# mainboard.net
KiCad netlist of a schematic drawn in EAGLE
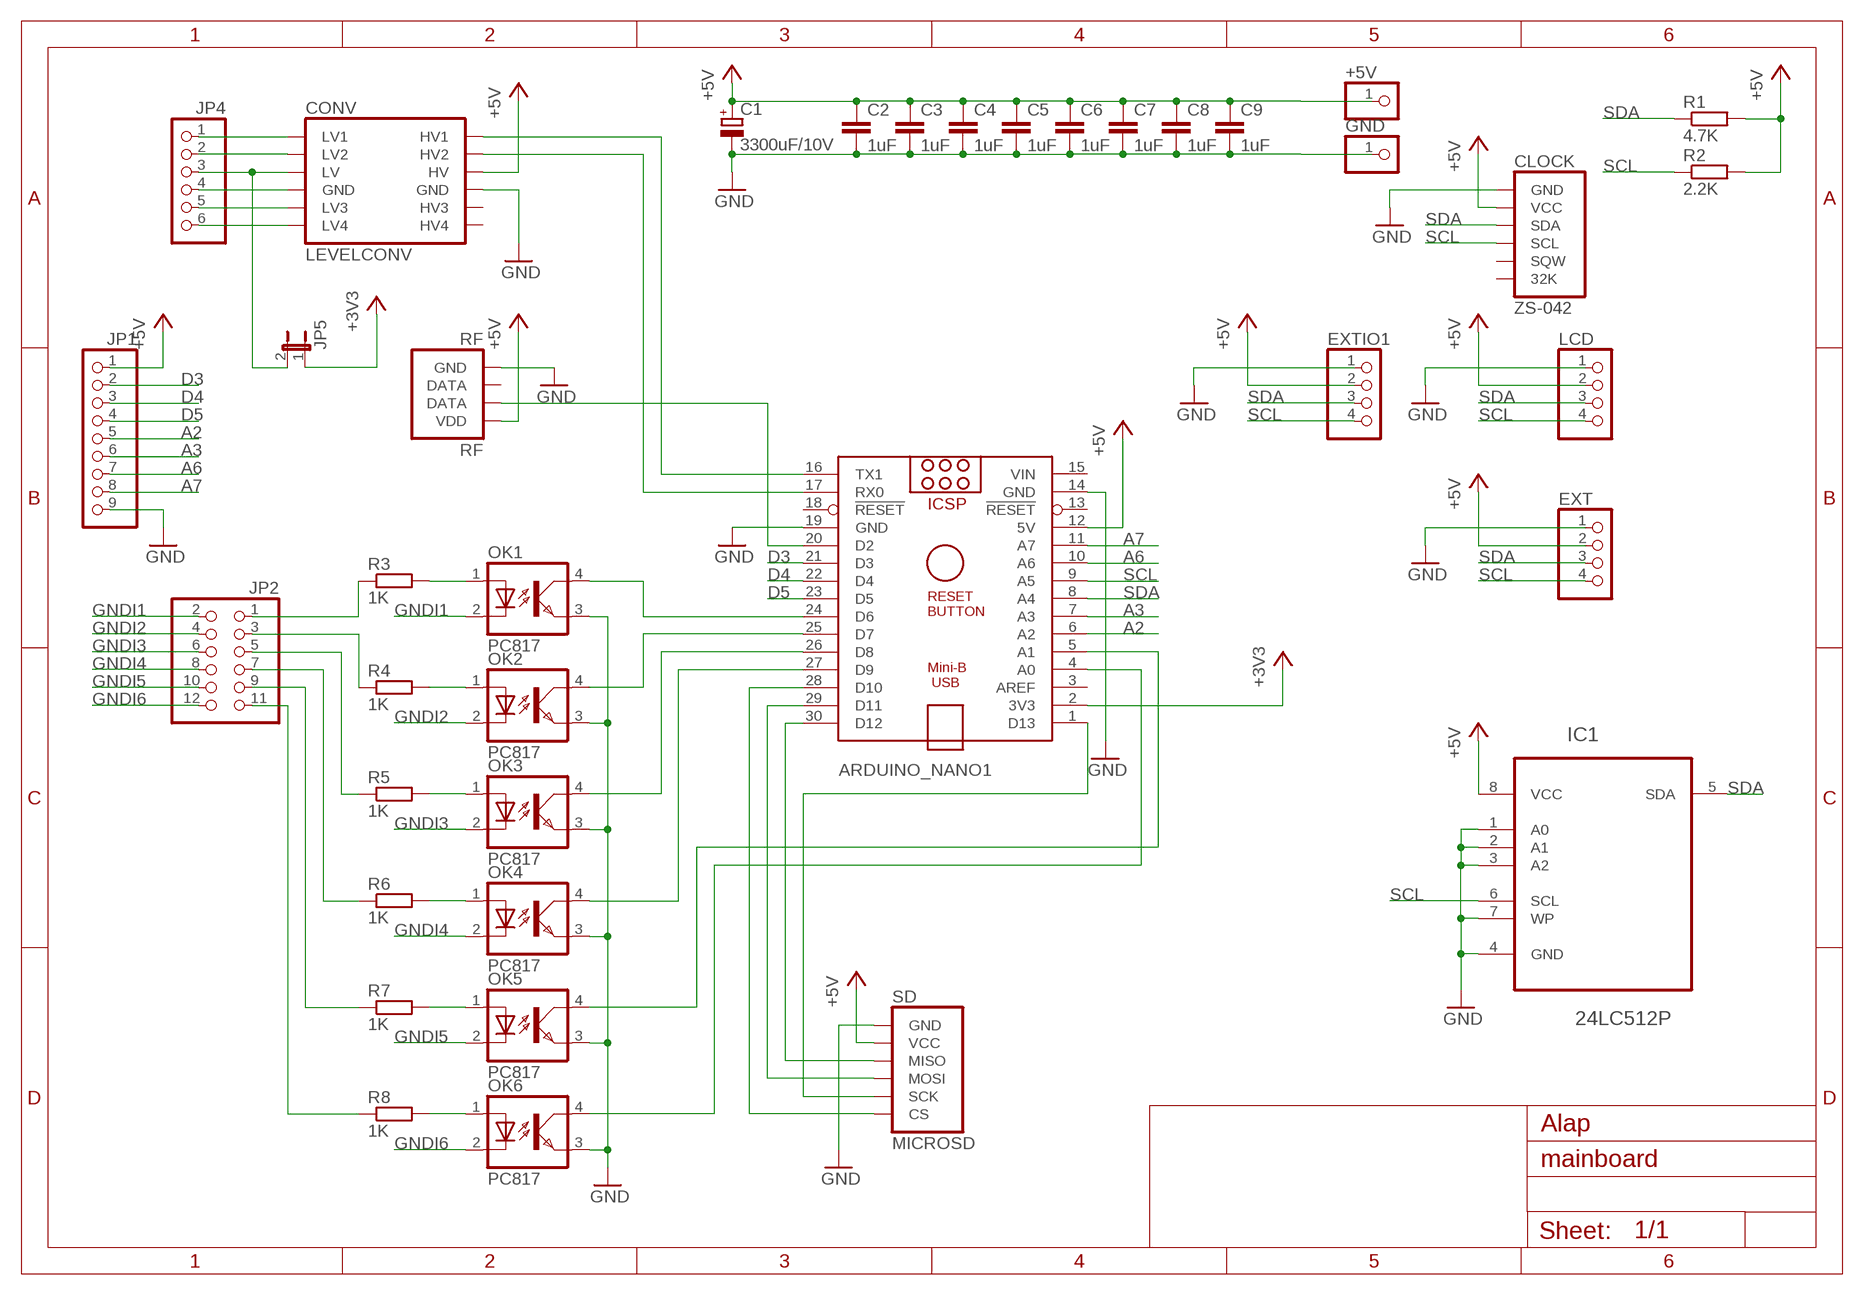
[diagram p0: schematic, sheet 1]

(export (version "E")
  (design (tool "Eeschema 10.0.6"))
  (components
    (comp (ref "+5V")
      (value "PINHD-1X1")
      (footprint "eagle-import:1X01")
      (libsource (lib "eagle-import") (part "PINHD-1X1"))
    )
    (comp (ref "ARDUINO_NANO1")
      (value "ARDUINO_NANO")
      (footprint "eagle-import:ARDUINO_NANO")
      (libsource (lib "eagle-import") (part "ARDUINO_NANO"))
    )
    (comp (ref "C1")
      (value "3300uF/10V")
      (footprint "eagle-import:E5-10,5")
      (libsource (lib "eagle-import") (part "CPOL-EUE5-10.5"))
    )
    (comp (ref "C2")
      (value "1uF")
      (footprint "eagle-import:C0603")
      (libsource (lib "eagle-import") (part "C-EUC0603"))
    )
    (comp (ref "C3")
      (value "1uF")
      (footprint "eagle-import:C0603")
      (libsource (lib "eagle-import") (part "C-EUC0603"))
    )
    (comp (ref "C4")
      (value "1uF")
      (footprint "eagle-import:C0603")
      (libsource (lib "eagle-import") (part "C-EUC0603"))
    )
    (comp (ref "C5")
      (value "1uF")
      (footprint "eagle-import:C0603")
      (libsource (lib "eagle-import") (part "C-EUC0603"))
    )
    (comp (ref "C6")
      (value "1uF")
      (footprint "eagle-import:C0603")
      (libsource (lib "eagle-import") (part "C-EUC0603"))
    )
    (comp (ref "C7")
      (value "1uF")
      (footprint "eagle-import:C0603")
      (libsource (lib "eagle-import") (part "C-EUC0603"))
    )
    (comp (ref "C8")
      (value "1uF")
      (footprint "eagle-import:C0603")
      (libsource (lib "eagle-import") (part "C-EUC0603"))
    )
    (comp (ref "C9")
      (value "1uF")
      (footprint "eagle-import:C0603")
      (libsource (lib "eagle-import") (part "C-EUC0603"))
    )
    (comp (ref "CLOCK")
      (value "ZS-042")
      (footprint "eagle-import:ZS-042")
      (libsource (lib "eagle-import") (part "ZS-042"))
    )
    (comp (ref "CONV")
      (value "LEVELCONV")
      (footprint "eagle-import:LEVELCONV")
      (libsource (lib "eagle-import") (part "LEVELCONV"))
    )
    (comp (ref "EXT")
      (value "PINHD-1X4")
      (footprint "eagle-import:1X04")
      (libsource (lib "eagle-import") (part "PINHD-1X4"))
    )
    (comp (ref "EXTIO1")
      (value "PINHD-1X4")
      (footprint "eagle-import:1X04")
      (libsource (lib "eagle-import") (part "PINHD-1X4"))
    )
    (comp (ref "GND")
      (value "PINHD-1X1")
      (footprint "eagle-import:1X01")
      (libsource (lib "eagle-import") (part "PINHD-1X1"))
    )
    (comp (ref "IC1")
      (value "24LC512P")
      (footprint "eagle-import:DIP254P762X533-8")
      (fields (field (name "MPN") "AT24C512B-PU25"))
      (libsource (lib "eagle-import") (part "AT24C512B-PU25"))
    )
    (comp (ref "JP1")
      (value "PINHD-1X9")
      (footprint "eagle-import:1X09")
      (libsource (lib "eagle-import") (part "PINHD-1X9"))
    )
    (comp (ref "JP2")
      (value "PINHD-2X6")
      (footprint "eagle-import:2X06")
      (libsource (lib "eagle-import") (part "PINHD-2X6"))
    )
    (comp (ref "JP4")
      (value "PINHD-1X6")
      (footprint "eagle-import:1X06")
      (libsource (lib "eagle-import") (part "PINHD-1X6"))
    )
    (comp (ref "JP5")
      (value "JP1E")
      (footprint "eagle-import:JP1")
      (libsource (lib "eagle-import") (part "JP1E"))
    )
    (comp (ref "LCD")
      (value "PINHD-1X4")
      (footprint "eagle-import:1X04")
      (libsource (lib "eagle-import") (part "PINHD-1X4"))
    )
    (comp (ref "OK1")
      (value "PC817")
      (footprint "eagle-import:DIL04")
      (fields (field (name "MPN") "PC817X4J000F"))
      (libsource (lib "eagle-import") (part "PC817"))
    )
    (comp (ref "OK2")
      (value "PC817")
      (footprint "eagle-import:DIL04")
      (fields (field (name "MPN") "PC817X4J000F"))
      (libsource (lib "eagle-import") (part "PC817"))
    )
    (comp (ref "OK3")
      (value "PC817")
      (footprint "eagle-import:DIL04")
      (fields (field (name "MPN") "PC817X4J000F"))
      (libsource (lib "eagle-import") (part "PC817"))
    )
    (comp (ref "OK4")
      (value "PC817")
      (footprint "eagle-import:DIL04")
      (fields (field (name "MPN") "PC817X4J000F"))
      (libsource (lib "eagle-import") (part "PC817"))
    )
    (comp (ref "OK5")
      (value "PC817")
      (footprint "eagle-import:DIL04")
      (fields (field (name "MPN") "PC817X4J000F"))
      (libsource (lib "eagle-import") (part "PC817"))
    )
    (comp (ref "OK6")
      (value "PC817")
      (footprint "eagle-import:DIL04")
      (fields (field (name "MPN") "PC817X4J000F"))
      (libsource (lib "eagle-import") (part "PC817"))
    )
    (comp (ref "R1")
      (value "4.7K")
      (footprint "eagle-import:R0603")
      (libsource (lib "eagle-import") (part "R-EU_R0603"))
    )
    (comp (ref "R2")
      (value "2.2K")
      (footprint "eagle-import:R0603")
      (libsource (lib "eagle-import") (part "R-EU_R0603"))
    )
    (comp (ref "R3")
      (value "1K")
      (footprint "eagle-import:R0603")
      (libsource (lib "eagle-import") (part "R-EU_R0603"))
    )
    (comp (ref "R4")
      (value "1K")
      (footprint "eagle-import:R0603")
      (libsource (lib "eagle-import") (part "R-EU_R0603"))
    )
    (comp (ref "R5")
      (value "1K")
      (footprint "eagle-import:R0603")
      (libsource (lib "eagle-import") (part "R-EU_R0603"))
    )
    (comp (ref "R6")
      (value "1K")
      (footprint "eagle-import:R0603")
      (libsource (lib "eagle-import") (part "R-EU_R0603"))
    )
    (comp (ref "R7")
      (value "1K")
      (footprint "eagle-import:R0603")
      (libsource (lib "eagle-import") (part "R-EU_R0603"))
    )
    (comp (ref "R8")
      (value "1K")
      (footprint "eagle-import:R0603")
      (libsource (lib "eagle-import") (part "R-EU_R0603"))
    )
    (comp (ref "RF") (value "RF") (footprint "eagle-import:RF") (libsource (lib "eagle-import") (part "RF")))
    (comp (ref "SD")
      (value "MICROSD")
      (footprint "eagle-import:MICROSD")
      (libsource (lib "eagle-import") (part "MICROSD"))
    )
  )
  (nets
    (net (code "1") (name "+3V3") (class "Default")
      (node (ref "ARDUINO_NANO1") (pin "2") (pinfunction "3V3_2") (pintype "output"))
      (node (ref "JP5") (pin "1") (pinfunction "1_1") (pintype "passive"))
    )
    (net (code "2") (name "+5V") (class "Default")
      (node (ref "+5V") (pin "1") (pinfunction "1_1") (pintype "passive"))
      (node (ref "ARDUINO_NANO1") (pin "12") (pinfunction "5V_12") (pintype "power_in"))
      (node (ref "C1") (pin "+") (pinfunction "+_+") (pintype "passive"))
      (node (ref "C2") (pin "1") (pinfunction "1_1") (pintype "passive"))
      (node (ref "C3") (pin "1") (pinfunction "1_1") (pintype "passive"))
      (node (ref "C4") (pin "1") (pinfunction "1_1") (pintype "passive"))
      (node (ref "C5") (pin "1") (pinfunction "1_1") (pintype "passive"))
      (node (ref "C6") (pin "1") (pinfunction "1_1") (pintype "passive"))
      (node (ref "C7") (pin "1") (pinfunction "1_1") (pintype "passive"))
      (node (ref "C8") (pin "1") (pinfunction "1_1") (pintype "passive"))
      (node (ref "C9") (pin "1") (pinfunction "1_1") (pintype "passive"))
      (node (ref "CLOCK") (pin "2") (pinfunction "VCC_2") (pintype "passive"))
      (node (ref "CONV") (pin "10") (pinfunction "HV_10") (pintype "bidirectional"))
      (node (ref "EXT") (pin "2") (pinfunction "2_2") (pintype "passive"))
      (node (ref "EXTIO1") (pin "2") (pinfunction "2_2") (pintype "passive"))
      (node (ref "IC1") (pin "8") (pinfunction "VCC_8") (pintype "power_in"))
      (node (ref "JP1") (pin "1") (pinfunction "1_1") (pintype "passive"))
      (node (ref "LCD") (pin "2") (pinfunction "2_2") (pintype "passive"))
      (node (ref "R1") (pin "2") (pinfunction "2_2") (pintype "passive"))
      (node (ref "R2") (pin "2") (pinfunction "2_2") (pintype "passive"))
      (node (ref "RF") (pin "4") (pinfunction "VDD_4") (pintype "passive"))
      (node (ref "SD") (pin "2") (pinfunction "VCC_2") (pintype "passive"))
    )
    (net (code "3") (name "/A2") (class "Default")
      (node (ref "ARDUINO_NANO1") (pin "6") (pinfunction "A2_6") (pintype "bidirectional"))
      (node (ref "JP1") (pin "5") (pinfunction "5_5") (pintype "passive"))
    )
    (net (code "4") (name "/A3") (class "Default")
      (node (ref "ARDUINO_NANO1") (pin "7") (pinfunction "A3_7") (pintype "bidirectional"))
      (node (ref "JP1") (pin "6") (pinfunction "6_6") (pintype "passive"))
    )
    (net (code "5") (name "/A6") (class "Default")
      (node (ref "ARDUINO_NANO1") (pin "10") (pinfunction "A6_10") (pintype "bidirectional"))
      (node (ref "JP1") (pin "7") (pinfunction "7_7") (pintype "passive"))
    )
    (net (code "6") (name "/A7") (class "Default")
      (node (ref "ARDUINO_NANO1") (pin "11") (pinfunction "A7_11") (pintype "bidirectional"))
      (node (ref "JP1") (pin "8") (pinfunction "8_8") (pintype "passive"))
    )
    (net (code "7") (name "/D3") (class "Default")
      (node (ref "ARDUINO_NANO1") (pin "21") (pinfunction "D3_21") (pintype "bidirectional"))
      (node (ref "JP1") (pin "2") (pinfunction "2_2") (pintype "passive"))
    )
    (net (code "8") (name "/D4") (class "Default")
      (node (ref "ARDUINO_NANO1") (pin "22") (pinfunction "D4_22") (pintype "bidirectional"))
      (node (ref "JP1") (pin "3") (pinfunction "3_3") (pintype "passive"))
    )
    (net (code "9") (name "/D5") (class "Default")
      (node (ref "ARDUINO_NANO1") (pin "23") (pinfunction "D5_23") (pintype "bidirectional"))
      (node (ref "JP1") (pin "4") (pinfunction "4_4") (pintype "passive"))
    )
    (net (code "10") (name "/GNDI1") (class "Default")
      (node (ref "JP2") (pin "2") (pinfunction "2_2") (pintype "passive"))
      (node (ref "OK1") (pin "2") (pinfunction "C_2") (pintype "passive"))
    )
    (net (code "11") (name "/GNDI2") (class "Default")
      (node (ref "JP2") (pin "4") (pinfunction "4_4") (pintype "passive"))
      (node (ref "OK2") (pin "2") (pinfunction "C_2") (pintype "passive"))
    )
    (net (code "12") (name "/GNDI3") (class "Default")
      (node (ref "JP2") (pin "6") (pinfunction "6_6") (pintype "passive"))
      (node (ref "OK3") (pin "2") (pinfunction "C_2") (pintype "passive"))
    )
    (net (code "13") (name "/GNDI4") (class "Default")
      (node (ref "JP2") (pin "8") (pinfunction "8_8") (pintype "passive"))
      (node (ref "OK4") (pin "2") (pinfunction "C_2") (pintype "passive"))
    )
    (net (code "14") (name "/GNDI5") (class "Default")
      (node (ref "JP2") (pin "10") (pinfunction "10_10") (pintype "passive"))
      (node (ref "OK5") (pin "2") (pinfunction "C_2") (pintype "passive"))
    )
    (net (code "15") (name "/GNDI6") (class "Default")
      (node (ref "JP2") (pin "12") (pinfunction "12_12") (pintype "passive"))
      (node (ref "OK6") (pin "2") (pinfunction "C_2") (pintype "passive"))
    )
    (net (code "16") (name "/SCL") (class "Default")
      (node (ref "ARDUINO_NANO1") (pin "9") (pinfunction "A5_9") (pintype "bidirectional"))
      (node (ref "CLOCK") (pin "4") (pinfunction "SCL_4") (pintype "passive"))
      (node (ref "EXT") (pin "4") (pinfunction "4_4") (pintype "passive"))
      (node (ref "EXTIO1") (pin "4") (pinfunction "4_4") (pintype "passive"))
      (node (ref "IC1") (pin "6") (pinfunction "SCL_6") (pintype "input"))
      (node (ref "LCD") (pin "4") (pinfunction "4_4") (pintype "passive"))
      (node (ref "R2") (pin "1") (pinfunction "1_1") (pintype "passive"))
    )
    (net (code "17") (name "/SDA") (class "Default")
      (node (ref "ARDUINO_NANO1") (pin "8") (pinfunction "A4_8") (pintype "bidirectional"))
      (node (ref "CLOCK") (pin "3") (pinfunction "SDA_3") (pintype "passive"))
      (node (ref "EXT") (pin "3") (pinfunction "3_3") (pintype "passive"))
      (node (ref "EXTIO1") (pin "3") (pinfunction "3_3") (pintype "passive"))
      (node (ref "IC1") (pin "5") (pinfunction "SDA_5") (pintype "bidirectional"))
      (node (ref "LCD") (pin "3") (pinfunction "3_3") (pintype "passive"))
      (node (ref "R1") (pin "1") (pinfunction "1_1") (pintype "passive"))
    )
    (net (code "18") (name "/VIN") (class "Default")
      (node (ref "ARDUINO_NANO1") (pin "15") (pinfunction "VIN_15") (pintype "power_in"))
    )
    (net (code "19") (name "GND") (class "Default")
      (node (ref "ARDUINO_NANO1") (pin "14") (pinfunction "GND_14") (pintype "power_in"))
      (node (ref "ARDUINO_NANO1") (pin "19") (pinfunction "GND_19") (pintype "power_in"))
      (node (ref "C1") (pin "-") (pinfunction "-_-") (pintype "passive"))
      (node (ref "C2") (pin "2") (pinfunction "2_2") (pintype "passive"))
      (node (ref "C3") (pin "2") (pinfunction "2_2") (pintype "passive"))
      (node (ref "C4") (pin "2") (pinfunction "2_2") (pintype "passive"))
      (node (ref "C5") (pin "2") (pinfunction "2_2") (pintype "passive"))
      (node (ref "C6") (pin "2") (pinfunction "2_2") (pintype "passive"))
      (node (ref "C7") (pin "2") (pinfunction "2_2") (pintype "passive"))
      (node (ref "C8") (pin "2") (pinfunction "2_2") (pintype "passive"))
      (node (ref "C9") (pin "2") (pinfunction "2_2") (pintype "passive"))
      (node (ref "CLOCK") (pin "1") (pinfunction "GND_1") (pintype "passive"))
      (node (ref "CONV") (pin "9") (pinfunction "GND_9") (pintype "bidirectional"))
      (node (ref "EXT") (pin "1") (pinfunction "1_1") (pintype "passive"))
      (node (ref "EXTIO1") (pin "1") (pinfunction "1_1") (pintype "passive"))
      (node (ref "GND") (pin "1") (pinfunction "1_1") (pintype "passive"))
      (node (ref "IC1") (pin "1") (pinfunction "A0_1") (pintype "input"))
      (node (ref "IC1") (pin "2") (pinfunction "A1_2") (pintype "input"))
      (node (ref "IC1") (pin "3") (pinfunction "A2_3") (pintype "input"))
      (node (ref "IC1") (pin "4") (pinfunction "GND_4") (pintype "passive"))
      (node (ref "IC1") (pin "7") (pinfunction "WP_7") (pintype "passive"))
      (node (ref "JP1") (pin "9") (pinfunction "9_9") (pintype "passive"))
      (node (ref "LCD") (pin "1") (pinfunction "1_1") (pintype "passive"))
      (node (ref "OK1") (pin "3") (pinfunction "EMIT_3") (pintype "passive"))
      (node (ref "OK2") (pin "3") (pinfunction "EMIT_3") (pintype "passive"))
      (node (ref "OK3") (pin "3") (pinfunction "EMIT_3") (pintype "passive"))
      (node (ref "OK4") (pin "3") (pinfunction "EMIT_3") (pintype "passive"))
      (node (ref "OK5") (pin "3") (pinfunction "EMIT_3") (pintype "passive"))
      (node (ref "OK6") (pin "3") (pinfunction "EMIT_3") (pintype "passive"))
      (node (ref "RF") (pin "1") (pinfunction "GND_1") (pintype "passive"))
      (node (ref "SD") (pin "1") (pinfunction "GND_1") (pintype "passive"))
    )
    (net (code "20") (name "Net-(ARDUINO_NANO1-A0)") (class "Default")
      (node (ref "ARDUINO_NANO1") (pin "4") (pinfunction "A0_4") (pintype "bidirectional"))
      (node (ref "OK6") (pin "4") (pinfunction "COL_4") (pintype "passive"))
    )
    (net (code "21") (name "Net-(ARDUINO_NANO1-A1)") (class "Default")
      (node (ref "ARDUINO_NANO1") (pin "5") (pinfunction "A1_5") (pintype "bidirectional"))
      (node (ref "OK5") (pin "4") (pinfunction "COL_4") (pintype "passive"))
    )
    (net (code "22") (name "Net-(ARDUINO_NANO1-D2)") (class "Default")
      (node (ref "ARDUINO_NANO1") (pin "20") (pinfunction "D2_20") (pintype "bidirectional"))
      (node (ref "RF") (pin "3") (pinfunction "DATA_3") (pintype "passive"))
    )
    (net (code "23") (name "Net-(ARDUINO_NANO1-D6)") (class "Default")
      (node (ref "ARDUINO_NANO1") (pin "24") (pinfunction "D6_24") (pintype "bidirectional"))
      (node (ref "OK1") (pin "4") (pinfunction "COL_4") (pintype "passive"))
    )
    (net (code "24") (name "Net-(ARDUINO_NANO1-D7)") (class "Default")
      (node (ref "ARDUINO_NANO1") (pin "25") (pinfunction "D7_25") (pintype "bidirectional"))
      (node (ref "OK2") (pin "4") (pinfunction "COL_4") (pintype "passive"))
    )
    (net (code "25") (name "Net-(ARDUINO_NANO1-D8)") (class "Default")
      (node (ref "ARDUINO_NANO1") (pin "26") (pinfunction "D8_26") (pintype "bidirectional"))
      (node (ref "OK3") (pin "4") (pinfunction "COL_4") (pintype "passive"))
    )
    (net (code "26") (name "Net-(ARDUINO_NANO1-D9)") (class "Default")
      (node (ref "ARDUINO_NANO1") (pin "27") (pinfunction "D9_27") (pintype "bidirectional"))
      (node (ref "OK4") (pin "4") (pinfunction "COL_4") (pintype "passive"))
    )
    (net (code "27") (name "Net-(ARDUINO_NANO1-D10)") (class "Default")
      (node (ref "ARDUINO_NANO1") (pin "28") (pinfunction "D10_28") (pintype "bidirectional"))
      (node (ref "SD") (pin "6") (pinfunction "CS_6") (pintype "passive"))
    )
    (net (code "28") (name "Net-(ARDUINO_NANO1-D11)") (class "Default")
      (node (ref "ARDUINO_NANO1") (pin "29") (pinfunction "D11_29") (pintype "bidirectional"))
      (node (ref "SD") (pin "4") (pinfunction "MOSI_4") (pintype "passive"))
    )
    (net (code "29") (name "Net-(ARDUINO_NANO1-D12)") (class "Default")
      (node (ref "ARDUINO_NANO1") (pin "30") (pinfunction "D12_30") (pintype "bidirectional"))
      (node (ref "SD") (pin "3") (pinfunction "MISO_3") (pintype "passive"))
    )
    (net (code "30") (name "Net-(ARDUINO_NANO1-D13)") (class "Default")
      (node (ref "ARDUINO_NANO1") (pin "1") (pinfunction "D13_1") (pintype "bidirectional"))
      (node (ref "SD") (pin "5") (pinfunction "SCK_5") (pintype "passive"))
    )
    (net (code "31") (name "Net-(ARDUINO_NANO1-RX0)") (class "Default")
      (node (ref "ARDUINO_NANO1") (pin "17") (pinfunction "RX0_17") (pintype "bidirectional"))
      (node (ref "CONV") (pin "11") (pinfunction "HV2_11") (pintype "bidirectional"))
    )
    (net (code "32") (name "Net-(ARDUINO_NANO1-TX1)") (class "Default")
      (node (ref "ARDUINO_NANO1") (pin "16") (pinfunction "TX1_16") (pintype "bidirectional"))
      (node (ref "CONV") (pin "12") (pinfunction "HV1_12") (pintype "bidirectional"))
    )
    (net (code "33") (name "Net-(CONV-GND-Pad4)") (class "Default")
      (node (ref "CONV") (pin "4") (pinfunction "GND_4") (pintype "passive"))
      (node (ref "JP4") (pin "4") (pinfunction "4_4") (pintype "passive"))
    )
    (net (code "34") (name "Net-(CONV-LV)") (class "Default")
      (node (ref "CONV") (pin "3") (pinfunction "LV_3") (pintype "passive"))
      (node (ref "JP4") (pin "3") (pinfunction "3_3") (pintype "passive"))
      (node (ref "JP5") (pin "2") (pinfunction "2_2") (pintype "passive"))
    )
    (net (code "35") (name "Net-(CONV-LV1)") (class "Default")
      (node (ref "CONV") (pin "1") (pinfunction "LV1_1") (pintype "passive"))
      (node (ref "JP4") (pin "1") (pinfunction "1_1") (pintype "passive"))
    )
    (net (code "36") (name "Net-(CONV-LV2)") (class "Default")
      (node (ref "CONV") (pin "2") (pinfunction "LV2_2") (pintype "passive"))
      (node (ref "JP4") (pin "2") (pinfunction "2_2") (pintype "passive"))
    )
    (net (code "37") (name "Net-(CONV-LV3)") (class "Default")
      (node (ref "CONV") (pin "5") (pinfunction "LV3_5") (pintype "passive"))
      (node (ref "JP4") (pin "5") (pinfunction "5_5") (pintype "passive"))
    )
    (net (code "38") (name "Net-(CONV-LV4)") (class "Default")
      (node (ref "CONV") (pin "6") (pinfunction "LV4_6") (pintype "passive"))
      (node (ref "JP4") (pin "6") (pinfunction "6_6") (pintype "passive"))
    )
    (net (code "39") (name "Net-(JP2-Pad1)") (class "Default")
      (node (ref "JP2") (pin "1") (pinfunction "1_1") (pintype "passive"))
      (node (ref "R3") (pin "1") (pinfunction "1_1") (pintype "passive"))
    )
    (net (code "40") (name "Net-(JP2-Pad3)") (class "Default")
      (node (ref "JP2") (pin "3") (pinfunction "3_3") (pintype "passive"))
      (node (ref "R4") (pin "1") (pinfunction "1_1") (pintype "passive"))
    )
    (net (code "41") (name "Net-(JP2-Pad5)") (class "Default")
      (node (ref "JP2") (pin "5") (pinfunction "5_5") (pintype "passive"))
      (node (ref "R5") (pin "1") (pinfunction "1_1") (pintype "passive"))
    )
    (net (code "42") (name "Net-(JP2-Pad7)") (class "Default")
      (node (ref "JP2") (pin "7") (pinfunction "7_7") (pintype "passive"))
      (node (ref "R6") (pin "1") (pinfunction "1_1") (pintype "passive"))
    )
    (net (code "43") (name "Net-(JP2-Pad9)") (class "Default")
      (node (ref "JP2") (pin "9") (pinfunction "9_9") (pintype "passive"))
      (node (ref "R7") (pin "1") (pinfunction "1_1") (pintype "passive"))
    )
    (net (code "44") (name "Net-(JP2-Pad11)") (class "Default")
      (node (ref "JP2") (pin "11") (pinfunction "11_11") (pintype "passive"))
      (node (ref "R8") (pin "1") (pinfunction "1_1") (pintype "passive"))
    )
    (net (code "45") (name "Net-(OK1-A)") (class "Default")
      (node (ref "OK1") (pin "1") (pinfunction "A_1") (pintype "passive"))
      (node (ref "R3") (pin "2") (pinfunction "2_2") (pintype "passive"))
    )
    (net (code "46") (name "Net-(OK2-A)") (class "Default")
      (node (ref "OK2") (pin "1") (pinfunction "A_1") (pintype "passive"))
      (node (ref "R4") (pin "2") (pinfunction "2_2") (pintype "passive"))
    )
    (net (code "47") (name "Net-(OK3-A)") (class "Default")
      (node (ref "OK3") (pin "1") (pinfunction "A_1") (pintype "passive"))
      (node (ref "R5") (pin "2") (pinfunction "2_2") (pintype "passive"))
    )
    (net (code "48") (name "Net-(OK4-A)") (class "Default")
      (node (ref "OK4") (pin "1") (pinfunction "A_1") (pintype "passive"))
      (node (ref "R6") (pin "2") (pinfunction "2_2") (pintype "passive"))
    )
    (net (code "49") (name "Net-(OK5-A)") (class "Default")
      (node (ref "OK5") (pin "1") (pinfunction "A_1") (pintype "passive"))
      (node (ref "R7") (pin "2") (pinfunction "2_2") (pintype "passive"))
    )
    (net (code "50") (name "Net-(OK6-A)") (class "Default")
      (node (ref "OK6") (pin "1") (pinfunction "A_1") (pintype "passive"))
      (node (ref "R8") (pin "2") (pinfunction "2_2") (pintype "passive"))
    )
    (net (code "51") (name "unconnected-(ARDUINO_NANO1-AREF-Pad3)") (class "Default")
      (node (ref "ARDUINO_NANO1") (pin "3") (pinfunction "AREF_3") (pintype "input"))
    )
    (net (code "52") (name "unconnected-(ARDUINO_NANO1-~{RESET}-Pad13)") (class "Default")
      (node (ref "ARDUINO_NANO1") (pin "13") (pinfunction "~{RESET}_13") (pintype "input"))
    )
    (net (code "53") (name "unconnected-(ARDUINO_NANO1-~{RESET}-Pad18)") (class "Default")
      (node (ref "ARDUINO_NANO1") (pin "18") (pinfunction "~{RESET}_18") (pintype "input"))
    )
    (net (code "54") (name "unconnected-(CLOCK-32K-Pad6)") (class "Default")
      (node (ref "CLOCK") (pin "6") (pinfunction "32K_6") (pintype "passive"))
    )
    (net (code "55") (name "unconnected-(CLOCK-SQW-Pad5)") (class "Default")
      (node (ref "CLOCK") (pin "5") (pinfunction "SQW_5") (pintype "passive"))
    )
    (net (code "56") (name "unconnected-(CONV-HV3-Pad8)") (class "Default")
      (node (ref "CONV") (pin "8") (pinfunction "HV3_8") (pintype "bidirectional"))
    )
    (net (code "57") (name "unconnected-(CONV-HV4-Pad7)") (class "Default")
      (node (ref "CONV") (pin "7") (pinfunction "HV4_7") (pintype "bidirectional"))
    )
    (net (code "58") (name "unconnected-(RF-DATA-Pad2)") (class "Default")
      (node (ref "RF") (pin "2") (pinfunction "DATA_2") (pintype "passive"))
    )
  )
)
